# circuit1.net
KiCad netlist of a schematic drawn in EAGLE
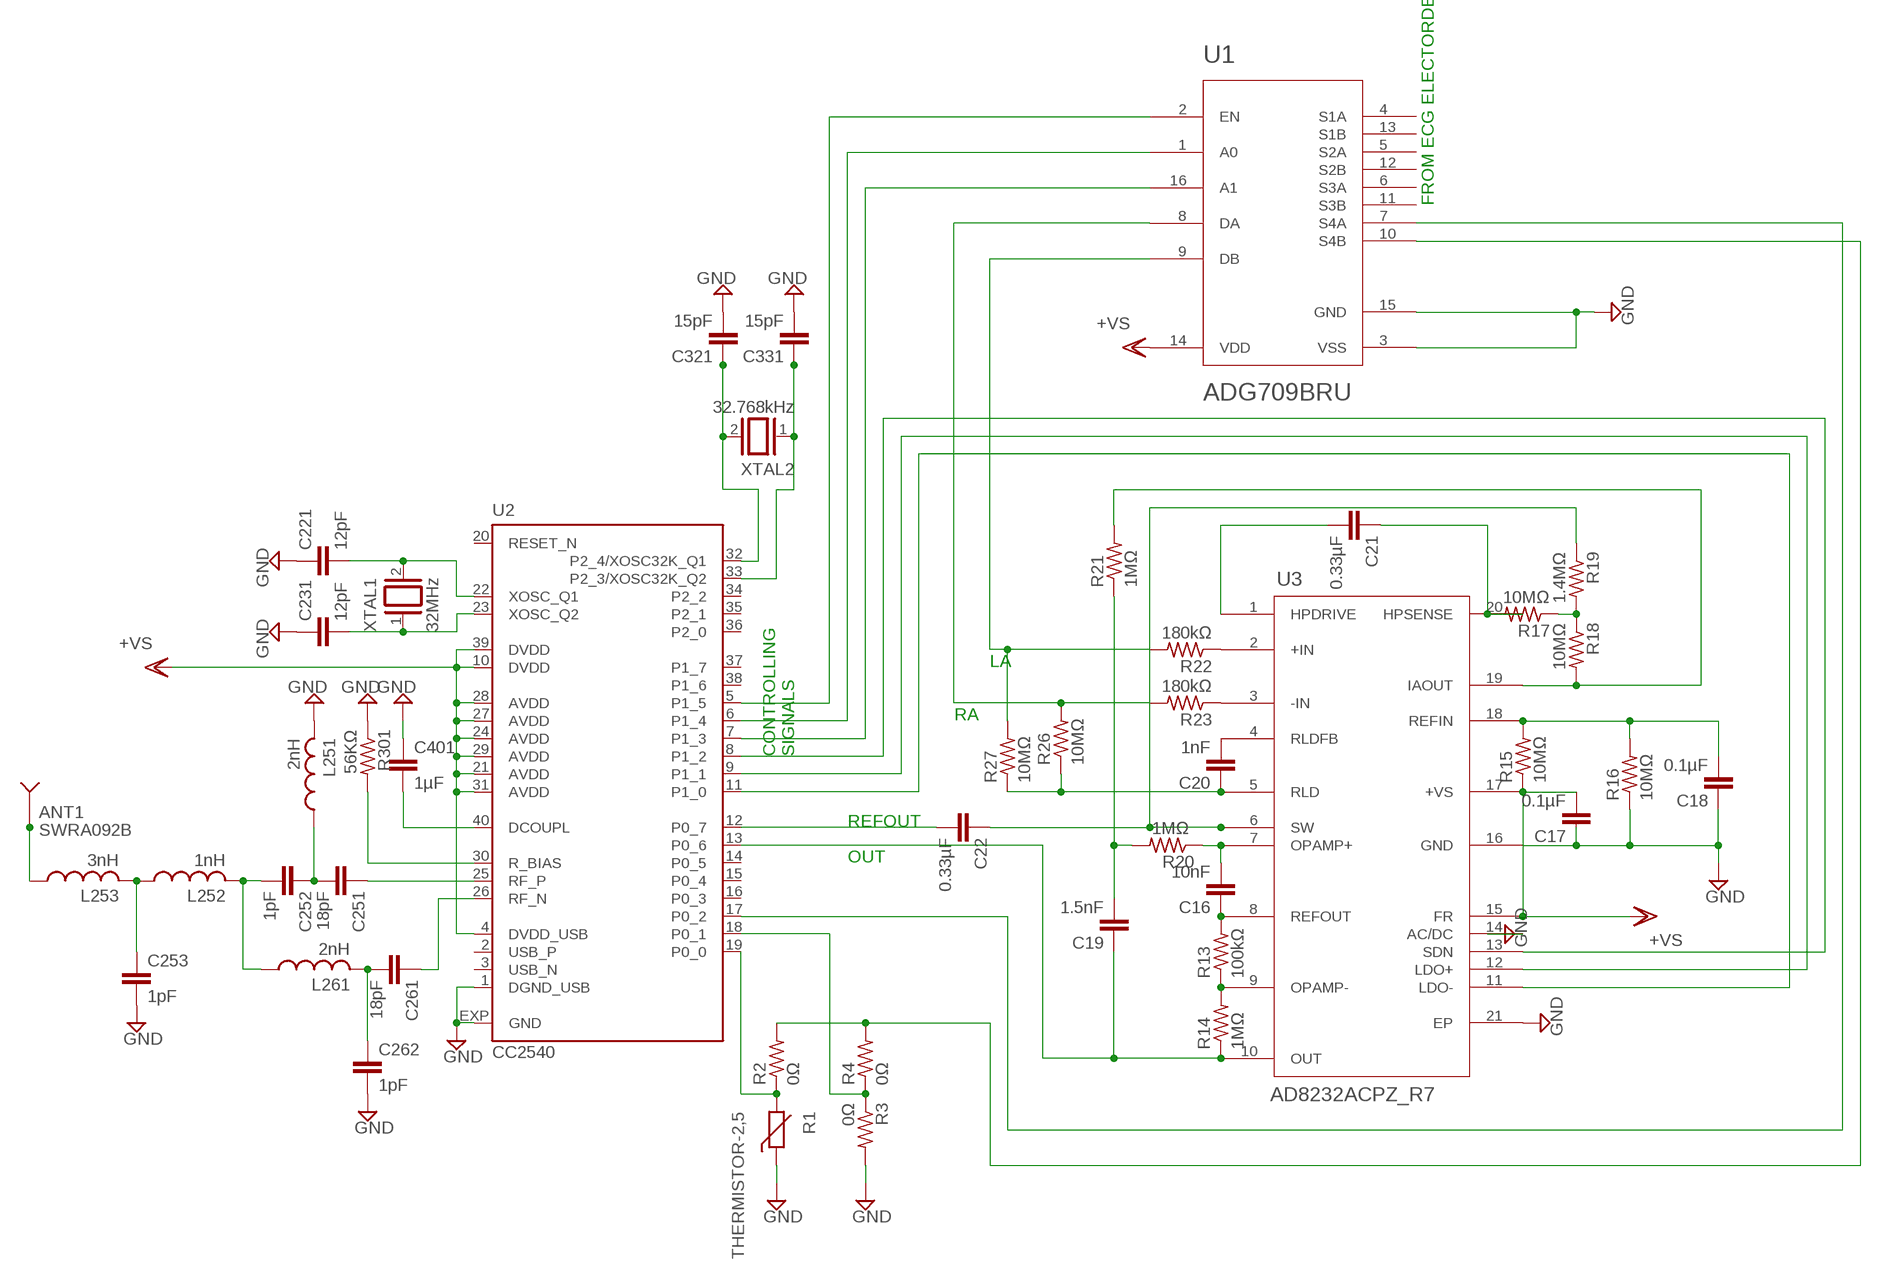
[diagram p0: schematic, sheet 1]

(export (version "E")
  (design (tool "Eeschema 10.0.6"))
  (components
    (comp (ref "ANT1")
      (value "SWRA092B")
      (footprint "eagle-import:SWRA092B")
      (libsource (lib "eagle-import") (part "SWRA092B"))
    )
    (comp (ref "C16")
      (value "10nF")
      (footprint "eagle-import:C0402")
      (libsource (lib "eagle-import") (part "C-EUC0402"))
    )
    (comp (ref "C17")
      (value "0.1µF")
      (footprint "eagle-import:C0402")
      (libsource (lib "eagle-import") (part "C-EUC0402"))
    )
    (comp (ref "C18")
      (value "0.1µF")
      (footprint "eagle-import:C0402")
      (libsource (lib "eagle-import") (part "C-EUC0402"))
    )
    (comp (ref "C19")
      (value "1.5nF")
      (footprint "eagle-import:C0402")
      (libsource (lib "eagle-import") (part "C-EUC0402"))
    )
    (comp (ref "C20")
      (value "1nF")
      (footprint "eagle-import:C0402")
      (libsource (lib "eagle-import") (part "C-EUC0402"))
    )
    (comp (ref "C21")
      (value "0.33µF")
      (footprint "eagle-import:C0402")
      (libsource (lib "eagle-import") (part "C-EUC0402"))
    )
    (comp (ref "C22")
      (value "0.33µF")
      (footprint "eagle-import:C0402")
      (libsource (lib "eagle-import") (part "C-EUC0402"))
    )
    (comp (ref "C221")
      (value "12pF")
      (footprint "eagle-import:C0402")
      (libsource (lib "eagle-import") (part "C-EUC0402"))
    )
    (comp (ref "C231")
      (value "12pF")
      (footprint "eagle-import:C0402")
      (libsource (lib "eagle-import") (part "C-EUC0402"))
    )
    (comp (ref "C251")
      (value "18pF")
      (footprint "eagle-import:C0402")
      (libsource (lib "eagle-import") (part "C-EUC0402"))
    )
    (comp (ref "C252")
      (value "1pF")
      (footprint "eagle-import:C0402")
      (libsource (lib "eagle-import") (part "C-EUC0402"))
    )
    (comp (ref "C253")
      (value "1pF")
      (footprint "eagle-import:C0402")
      (libsource (lib "eagle-import") (part "C-EUC0402"))
    )
    (comp (ref "C261")
      (value "18pF")
      (footprint "eagle-import:C0402")
      (libsource (lib "eagle-import") (part "C-EUC0402"))
    )
    (comp (ref "C262")
      (value "1pF")
      (footprint "eagle-import:C0402")
      (libsource (lib "eagle-import") (part "C-EUC0402"))
    )
    (comp (ref "C321")
      (value "15pF")
      (footprint "eagle-import:C0402")
      (libsource (lib "eagle-import") (part "C-EUC0402"))
    )
    (comp (ref "C331")
      (value "15pF")
      (footprint "eagle-import:C0402")
      (libsource (lib "eagle-import") (part "C-EUC0402"))
    )
    (comp (ref "C401")
      (value "1µF")
      (footprint "eagle-import:C0402")
      (libsource (lib "eagle-import") (part "C-EUC0402"))
    )
    (comp (ref "L251")
      (value "2nH")
      (footprint "eagle-import:0204_5")
      (libsource (lib "eagle-import") (part "L-US0204/5"))
    )
    (comp (ref "L252")
      (value "1nH")
      (footprint "eagle-import:0204_5")
      (libsource (lib "eagle-import") (part "L-US0204/5"))
    )
    (comp (ref "L253")
      (value "3nH")
      (footprint "eagle-import:0204_5")
      (libsource (lib "eagle-import") (part "L-US0204/5"))
    )
    (comp (ref "L261")
      (value "2nH")
      (footprint "eagle-import:0204_5")
      (libsource (lib "eagle-import") (part "L-US0204/5"))
    )
    (comp (ref "R1")
      (value "THERMISTOR-2,5")
      (footprint "eagle-import:RS-2,5")
      (libsource (lib "eagle-import") (part "THERMISTOR-2,5"))
    )
    (comp (ref "R2")
      (value "0Ω")
      (footprint "eagle-import:R0402")
      (libsource (lib "eagle-import") (part "R-US_R0402"))
    )
    (comp (ref "R3")
      (value "0Ω")
      (footprint "eagle-import:R0402")
      (libsource (lib "eagle-import") (part "R-US_R0402"))
    )
    (comp (ref "R4")
      (value "0Ω")
      (footprint "eagle-import:R0402")
      (libsource (lib "eagle-import") (part "R-US_R0402"))
    )
    (comp (ref "R13")
      (value "100kΩ")
      (footprint "eagle-import:R0402")
      (libsource (lib "eagle-import") (part "R-US_R0402"))
    )
    (comp (ref "R14")
      (value "1MΩ")
      (footprint "eagle-import:R0402")
      (libsource (lib "eagle-import") (part "R-US_R0402"))
    )
    (comp (ref "R15")
      (value "10MΩ")
      (footprint "eagle-import:R0402")
      (libsource (lib "eagle-import") (part "R-US_R0402"))
    )
    (comp (ref "R16")
      (value "10MΩ")
      (footprint "eagle-import:R0402")
      (libsource (lib "eagle-import") (part "R-US_R0402"))
    )
    (comp (ref "R17")
      (value "10MΩ")
      (footprint "eagle-import:R0402")
      (libsource (lib "eagle-import") (part "R-US_R0402"))
    )
    (comp (ref "R18")
      (value "10MΩ")
      (footprint "eagle-import:R0402")
      (libsource (lib "eagle-import") (part "R-US_R0402"))
    )
    (comp (ref "R19")
      (value "1.4MΩ")
      (footprint "eagle-import:R0402")
      (libsource (lib "eagle-import") (part "R-US_R0402"))
    )
    (comp (ref "R20")
      (value "1MΩ")
      (footprint "eagle-import:R0402")
      (libsource (lib "eagle-import") (part "R-US_R0402"))
    )
    (comp (ref "R21")
      (value "1MΩ")
      (footprint "eagle-import:R0402")
      (libsource (lib "eagle-import") (part "R-US_R0402"))
    )
    (comp (ref "R22")
      (value "180kΩ")
      (footprint "eagle-import:R0402")
      (libsource (lib "eagle-import") (part "R-US_R0402"))
    )
    (comp (ref "R23")
      (value "180kΩ")
      (footprint "eagle-import:R0402")
      (libsource (lib "eagle-import") (part "R-US_R0402"))
    )
    (comp (ref "R26")
      (value "10MΩ")
      (footprint "eagle-import:R0402")
      (libsource (lib "eagle-import") (part "R-US_R0402"))
    )
    (comp (ref "R27")
      (value "10MΩ")
      (footprint "eagle-import:R0402")
      (libsource (lib "eagle-import") (part "R-US_R0402"))
    )
    (comp (ref "R301")
      (value "56KΩ")
      (footprint "eagle-import:R0402")
      (libsource (lib "eagle-import") (part "R-US_R0402"))
    )
    (comp (ref "U1")
      (value "ADG709BRU")
      (footprint "eagle-import:RU_16")
      (libsource (lib "eagle-import") (part "ADG709BRU"))
    )
    (comp (ref "U2")
      (value "CC2540")
      (footprint "eagle-import:RHA_S-PVQFN-N40")
      (libsource (lib "eagle-import") (part "CC2540"))
    )
    (comp (ref "U3")
      (value "AD8232ACPZ_R7")
      (footprint "eagle-import:CP_20_10")
      (libsource (lib "eagle-import") (part "AD8232ACPZ_R7"))
    )
    (comp (ref "XTAL1")
      (value "32MHz")
      (footprint "eagle-import:Q")
      (libsource (lib "eagle-import") (part "XTAL"))
    )
    (comp (ref "XTAL2")
      (value "32.768kHz")
      (footprint "eagle-import:Q")
      (libsource (lib "eagle-import") (part "XTAL"))
    )
  )
  (nets
    (net (code "1") (name "+VS") (class "Default")
      (node (ref "C17") (pin "2") (pinfunction "2_2") (pintype "passive"))
      (node (ref "R15") (pin "1") (pinfunction "1_1") (pintype "passive"))
      (node (ref "U1") (pin "14") (pinfunction "VDD_14") (pintype "power_in"))
      (node (ref "U2") (pin "10") (pinfunction "DVDD_10") (pintype "power_in"))
      (node (ref "U2") (pin "21") (pinfunction "AVDD_21") (pintype "power_in"))
      (node (ref "U2") (pin "24") (pinfunction "AVDD_24") (pintype "power_in"))
      (node (ref "U2") (pin "27") (pinfunction "AVDD_27") (pintype "power_in"))
      (node (ref "U2") (pin "28") (pinfunction "AVDD_28") (pintype "power_in"))
      (node (ref "U2") (pin "29") (pinfunction "AVDD_29") (pintype "power_in"))
      (node (ref "U2") (pin "31") (pinfunction "AVDD_31") (pintype "power_in"))
      (node (ref "U2") (pin "39") (pinfunction "DVDD_39") (pintype "power_in"))
      (node (ref "U2") (pin "4") (pinfunction "DVDD_USB_4") (pintype "power_in"))
      (node (ref "U3") (pin "15") (pinfunction "FR_15") (pintype "passive"))
      (node (ref "U3") (pin "17") (pinfunction "+VS_17") (pintype "passive"))
    )
    (net (code "2") (name "GND") (class "Default")
      (node (ref "C17") (pin "1") (pinfunction "1_1") (pintype "passive"))
      (node (ref "C18") (pin "1") (pinfunction "1_1") (pintype "passive"))
      (node (ref "C221") (pin "1") (pinfunction "1_1") (pintype "passive"))
      (node (ref "C231") (pin "1") (pinfunction "1_1") (pintype "passive"))
      (node (ref "C253") (pin "2") (pinfunction "2_2") (pintype "passive"))
      (node (ref "C262") (pin "2") (pinfunction "2_2") (pintype "passive"))
      (node (ref "C321") (pin "2") (pinfunction "2_2") (pintype "passive"))
      (node (ref "C331") (pin "2") (pinfunction "2_2") (pintype "passive"))
      (node (ref "C401") (pin "1") (pinfunction "1_1") (pintype "passive"))
      (node (ref "L251") (pin "2") (pinfunction "2_2") (pintype "passive"))
      (node (ref "R1") (pin "1") (pinfunction "1_1") (pintype "passive"))
      (node (ref "R16") (pin "1") (pinfunction "1_1") (pintype "passive"))
      (node (ref "R3") (pin "2") (pinfunction "2_2") (pintype "passive"))
      (node (ref "R301") (pin "1") (pinfunction "1_1") (pintype "passive"))
      (node (ref "U1") (pin "15") (pinfunction "GND_15") (pintype "passive"))
      (node (ref "U1") (pin "3") (pinfunction "VSS_3") (pintype "power_in"))
      (node (ref "U2") (pin "1") (pinfunction "DGND_USB_1") (pintype "power_in"))
      (node (ref "U2") (pin "EXP") (pinfunction "GND_EXP") (pintype "passive"))
      (node (ref "U3") (pin "14") (pinfunction "AC/DC_14") (pintype "passive"))
      (node (ref "U3") (pin "16") (pinfunction "GND_16") (pintype "passive"))
      (node (ref "U3") (pin "21") (pinfunction "EP_21") (pintype "passive"))
    )
    (net (code "3") (name "Net-(ANT1-ANTENNA)") (class "Default")
      (node (ref "ANT1") (pin "1") (pinfunction "ANTENNA_1") (pintype "input"))
      (node (ref "L253") (pin "1") (pinfunction "1_1") (pintype "passive"))
    )
    (net (code "4") (name "Net-(C19-Pad2)") (class "Default")
      (node (ref "C19") (pin "2") (pinfunction "2_2") (pintype "passive"))
      (node (ref "R20") (pin "2") (pinfunction "2_2") (pintype "passive"))
      (node (ref "R21") (pin "1") (pinfunction "1_1") (pintype "passive"))
    )
    (net (code "5") (name "Net-(C251-Pad2)") (class "Default")
      (node (ref "C251") (pin "2") (pinfunction "2_2") (pintype "passive"))
      (node (ref "C252") (pin "1") (pinfunction "1_1") (pintype "passive"))
      (node (ref "L251") (pin "1") (pinfunction "1_1") (pintype "passive"))
    )
    (net (code "6") (name "Net-(C252-Pad2)") (class "Default")
      (node (ref "C252") (pin "2") (pinfunction "2_2") (pintype "passive"))
      (node (ref "L252") (pin "2") (pinfunction "2_2") (pintype "passive"))
      (node (ref "L261") (pin "1") (pinfunction "1_1") (pintype "passive"))
    )
    (net (code "7") (name "Net-(C253-Pad1)") (class "Default")
      (node (ref "C253") (pin "1") (pinfunction "1_1") (pintype "passive"))
      (node (ref "L252") (pin "1") (pinfunction "1_1") (pintype "passive"))
      (node (ref "L253") (pin "2") (pinfunction "2_2") (pintype "passive"))
    )
    (net (code "8") (name "Net-(C261-Pad2)") (class "Default")
      (node (ref "C261") (pin "2") (pinfunction "2_2") (pintype "passive"))
      (node (ref "C262") (pin "1") (pinfunction "1_1") (pintype "passive"))
      (node (ref "L261") (pin "2") (pinfunction "2_2") (pintype "passive"))
    )
    (net (code "9") (name "Net-(R17-Pad1)") (class "Default")
      (node (ref "R17") (pin "1") (pinfunction "1_1") (pintype "passive"))
      (node (ref "R18") (pin "1") (pinfunction "1_1") (pintype "passive"))
      (node (ref "R19") (pin "2") (pinfunction "2_2") (pintype "passive"))
    )
    (net (code "10") (name "Net-(U1-A0)") (class "Default")
      (node (ref "U1") (pin "1") (pinfunction "A0_1") (pintype "passive"))
      (node (ref "U2") (pin "6") (pinfunction "P1_4_6") (pintype "bidirectional"))
    )
    (net (code "11") (name "Net-(U1-A1)") (class "Default")
      (node (ref "U1") (pin "16") (pinfunction "A1_16") (pintype "passive"))
      (node (ref "U2") (pin "7") (pinfunction "P1_3_7") (pintype "bidirectional"))
    )
    (net (code "12") (name "Net-(U1-DA)") (class "Default")
      (node (ref "R23") (pin "2") (pinfunction "2_2") (pintype "passive"))
      (node (ref "R26") (pin "2") (pinfunction "2_2") (pintype "passive"))
      (node (ref "U1") (pin "8") (pinfunction "DA_8") (pintype "passive"))
    )
    (net (code "13") (name "Net-(U1-DB)") (class "Default")
      (node (ref "R22") (pin "2") (pinfunction "2_2") (pintype "passive"))
      (node (ref "R27") (pin "2") (pinfunction "2_2") (pintype "passive"))
      (node (ref "U1") (pin "9") (pinfunction "DB_9") (pintype "passive"))
    )
    (net (code "14") (name "Net-(U1-EN)") (class "Default")
      (node (ref "U1") (pin "2") (pinfunction "EN_2") (pintype "passive"))
      (node (ref "U2") (pin "5") (pinfunction "P1_5_5") (pintype "bidirectional"))
    )
    (net (code "15") (name "Net-(U1-S4A)") (class "Default")
      (node (ref "U1") (pin "7") (pinfunction "S4A_7") (pintype "passive"))
      (node (ref "U2") (pin "17") (pinfunction "P0_2_17") (pintype "bidirectional"))
    )
    (net (code "16") (name "Net-(U1-S4B)") (class "Default")
      (node (ref "R2") (pin "2") (pinfunction "2_2") (pintype "passive"))
      (node (ref "R4") (pin "2") (pinfunction "2_2") (pintype "passive"))
      (node (ref "U1") (pin "10") (pinfunction "S4B_10") (pintype "passive"))
    )
    (net (code "17") (name "Net-(U2-DCOUPL)") (class "Default")
      (node (ref "C401") (pin "2") (pinfunction "2_2") (pintype "passive"))
      (node (ref "U2") (pin "40") (pinfunction "DCOUPL_40") (pintype "power_in"))
    )
    (net (code "18") (name "Net-(U2-P0_0)") (class "Default")
      (node (ref "R1") (pin "2") (pinfunction "2_2") (pintype "passive"))
      (node (ref "R2") (pin "1") (pinfunction "1_1") (pintype "passive"))
      (node (ref "U2") (pin "19") (pinfunction "P0_0_19") (pintype "bidirectional"))
    )
    (net (code "19") (name "Net-(U2-P0_1)") (class "Default")
      (node (ref "R3") (pin "1") (pinfunction "1_1") (pintype "passive"))
      (node (ref "R4") (pin "1") (pinfunction "1_1") (pintype "passive"))
      (node (ref "U2") (pin "18") (pinfunction "P0_1_18") (pintype "bidirectional"))
    )
    (net (code "20") (name "Net-(U2-P0_6)") (class "Default")
      (node (ref "C19") (pin "1") (pinfunction "1_1") (pintype "passive"))
      (node (ref "R14") (pin "1") (pinfunction "1_1") (pintype "passive"))
      (node (ref "U2") (pin "13") (pinfunction "P0_6_13") (pintype "bidirectional"))
      (node (ref "U3") (pin "10") (pinfunction "OUT_10") (pintype "passive"))
    )
    (net (code "21") (name "Net-(U2-P0_7)") (class "Default")
      (node (ref "C22") (pin "2") (pinfunction "2_2") (pintype "passive"))
      (node (ref "U2") (pin "12") (pinfunction "P0_7_12") (pintype "bidirectional"))
    )
    (net (code "22") (name "Net-(U2-P1_0)") (class "Default")
      (node (ref "U2") (pin "11") (pinfunction "P1_0_11") (pintype "bidirectional"))
      (node (ref "U3") (pin "11") (pinfunction "LDO-_11") (pintype "passive"))
    )
    (net (code "23") (name "Net-(U2-P1_1)") (class "Default")
      (node (ref "U2") (pin "9") (pinfunction "P1_1_9") (pintype "bidirectional"))
      (node (ref "U3") (pin "12") (pinfunction "LDO+_12") (pintype "passive"))
    )
    (net (code "24") (name "Net-(U2-P1_2)") (class "Default")
      (node (ref "U2") (pin "8") (pinfunction "P1_2_8") (pintype "bidirectional"))
      (node (ref "U3") (pin "13") (pinfunction "SDN_13") (pintype "passive"))
    )
    (net (code "25") (name "Net-(U2-P2_3{slash}XOSC32K_Q2)") (class "Default")
      (node (ref "C331") (pin "1") (pinfunction "1_1") (pintype "passive"))
      (node (ref "U2") (pin "33") (pinfunction "P2_3/XOSC32K_Q2_33") (pintype "bidirectional"))
      (node (ref "XTAL2") (pin "1") (pinfunction "1_1") (pintype "passive"))
    )
    (net (code "26") (name "Net-(U2-P2_4{slash}XOSC32K_Q1)") (class "Default")
      (node (ref "C321") (pin "1") (pinfunction "1_1") (pintype "passive"))
      (node (ref "U2") (pin "32") (pinfunction "P2_4/XOSC32K_Q1_32") (pintype "bidirectional"))
      (node (ref "XTAL2") (pin "2") (pinfunction "2_2") (pintype "passive"))
    )
    (net (code "27") (name "Net-(U2-RF_N)") (class "Default")
      (node (ref "C261") (pin "1") (pinfunction "1_1") (pintype "passive"))
      (node (ref "U2") (pin "26") (pinfunction "RF_N_26") (pintype "bidirectional"))
    )
    (net (code "28") (name "Net-(U2-RF_P)") (class "Default")
      (node (ref "C251") (pin "1") (pinfunction "1_1") (pintype "passive"))
      (node (ref "U2") (pin "25") (pinfunction "RF_P_25") (pintype "bidirectional"))
    )
    (net (code "29") (name "Net-(U2-R_BIAS)") (class "Default")
      (node (ref "R301") (pin "2") (pinfunction "2_2") (pintype "passive"))
      (node (ref "U2") (pin "30") (pinfunction "R_BIAS_30") (pintype "bidirectional"))
    )
    (net (code "30") (name "Net-(U2-XOSC_Q1)") (class "Default")
      (node (ref "C221") (pin "2") (pinfunction "2_2") (pintype "passive"))
      (node (ref "U2") (pin "22") (pinfunction "XOSC_Q1_22") (pintype "bidirectional"))
      (node (ref "XTAL1") (pin "2") (pinfunction "2_2") (pintype "passive"))
    )
    (net (code "31") (name "Net-(U2-XOSC_Q2)") (class "Default")
      (node (ref "C231") (pin "2") (pinfunction "2_2") (pintype "passive"))
      (node (ref "U2") (pin "23") (pinfunction "XOSC_Q2_23") (pintype "bidirectional"))
      (node (ref "XTAL1") (pin "1") (pinfunction "1_1") (pintype "passive"))
    )
    (net (code "32") (name "Net-(U3-+IN)") (class "Default")
      (node (ref "R22") (pin "1") (pinfunction "1_1") (pintype "passive"))
      (node (ref "U3") (pin "2") (pinfunction "+IN_2") (pintype "passive"))
    )
    (net (code "33") (name "Net-(U3--IN)") (class "Default")
      (node (ref "R23") (pin "1") (pinfunction "1_1") (pintype "passive"))
      (node (ref "U3") (pin "3") (pinfunction "-IN_3") (pintype "passive"))
    )
    (net (code "34") (name "Net-(U3-HPDRIVE)") (class "Default")
      (node (ref "C21") (pin "2") (pinfunction "2_2") (pintype "passive"))
      (node (ref "U3") (pin "1") (pinfunction "HPDRIVE_1") (pintype "passive"))
    )
    (net (code "35") (name "Net-(U3-HPSENSE)") (class "Default")
      (node (ref "C21") (pin "1") (pinfunction "1_1") (pintype "passive"))
      (node (ref "R17") (pin "2") (pinfunction "2_2") (pintype "passive"))
      (node (ref "U3") (pin "20") (pinfunction "HPSENSE_20") (pintype "passive"))
    )
    (net (code "36") (name "Net-(U3-IAOUT)") (class "Default")
      (node (ref "R18") (pin "2") (pinfunction "2_2") (pintype "passive"))
      (node (ref "R21") (pin "2") (pinfunction "2_2") (pintype "passive"))
      (node (ref "U3") (pin "19") (pinfunction "IAOUT_19") (pintype "passive"))
    )
    (net (code "37") (name "Net-(U3-OPAMP+)") (class "Default")
      (node (ref "C16") (pin "2") (pinfunction "2_2") (pintype "passive"))
      (node (ref "R20") (pin "1") (pinfunction "1_1") (pintype "passive"))
      (node (ref "U3") (pin "7") (pinfunction "OPAMP+_7") (pintype "passive"))
    )
    (net (code "38") (name "Net-(U3-OPAMP-)") (class "Default")
      (node (ref "R13") (pin "1") (pinfunction "1_1") (pintype "passive"))
      (node (ref "R14") (pin "2") (pinfunction "2_2") (pintype "passive"))
      (node (ref "U3") (pin "9") (pinfunction "OPAMP-_9") (pintype "passive"))
    )
    (net (code "39") (name "Net-(U3-REFIN)") (class "Default")
      (node (ref "C18") (pin "2") (pinfunction "2_2") (pintype "passive"))
      (node (ref "R15") (pin "2") (pinfunction "2_2") (pintype "passive"))
      (node (ref "R16") (pin "2") (pinfunction "2_2") (pintype "passive"))
      (node (ref "U3") (pin "18") (pinfunction "REFIN_18") (pintype "passive"))
    )
    (net (code "40") (name "Net-(U3-REFOUT)") (class "Default")
      (node (ref "C16") (pin "1") (pinfunction "1_1") (pintype "passive"))
      (node (ref "R13") (pin "2") (pinfunction "2_2") (pintype "passive"))
      (node (ref "U3") (pin "8") (pinfunction "REFOUT_8") (pintype "passive"))
    )
    (net (code "41") (name "Net-(U3-RLD)") (class "Default")
      (node (ref "C20") (pin "1") (pinfunction "1_1") (pintype "passive"))
      (node (ref "R26") (pin "1") (pinfunction "1_1") (pintype "passive"))
      (node (ref "R27") (pin "1") (pinfunction "1_1") (pintype "passive"))
      (node (ref "U3") (pin "5") (pinfunction "RLD_5") (pintype "passive"))
    )
    (net (code "42") (name "Net-(U3-RLDFB)") (class "Default")
      (node (ref "C20") (pin "2") (pinfunction "2_2") (pintype "passive"))
      (node (ref "U3") (pin "4") (pinfunction "RLDFB_4") (pintype "passive"))
    )
    (net (code "43") (name "Net-(U3-SW)") (class "Default")
      (node (ref "C22") (pin "1") (pinfunction "1_1") (pintype "passive"))
      (node (ref "R19") (pin "1") (pinfunction "1_1") (pintype "passive"))
      (node (ref "U3") (pin "6") (pinfunction "SW_6") (pintype "passive"))
    )
    (net (code "44") (name "unconnected-(U1-S1A-Pad4)") (class "Default")
      (node (ref "U1") (pin "4") (pinfunction "S1A_4") (pintype "passive"))
    )
    (net (code "45") (name "unconnected-(U1-S1B-Pad13)") (class "Default")
      (node (ref "U1") (pin "13") (pinfunction "S1B_13") (pintype "passive"))
    )
    (net (code "46") (name "unconnected-(U1-S2A-Pad5)") (class "Default")
      (node (ref "U1") (pin "5") (pinfunction "S2A_5") (pintype "passive"))
    )
    (net (code "47") (name "unconnected-(U1-S2B-Pad12)") (class "Default")
      (node (ref "U1") (pin "12") (pinfunction "S2B_12") (pintype "passive"))
    )
    (net (code "48") (name "unconnected-(U1-S3A-Pad6)") (class "Default")
      (node (ref "U1") (pin "6") (pinfunction "S3A_6") (pintype "passive"))
    )
    (net (code "49") (name "unconnected-(U1-S3B-Pad11)") (class "Default")
      (node (ref "U1") (pin "11") (pinfunction "S3B_11") (pintype "passive"))
    )
    (net (code "50") (name "unconnected-(U2-P0_3-Pad16)") (class "Default")
      (node (ref "U2") (pin "16") (pinfunction "P0_3_16") (pintype "bidirectional"))
    )
    (net (code "51") (name "unconnected-(U2-P0_4-Pad15)") (class "Default")
      (node (ref "U2") (pin "15") (pinfunction "P0_4_15") (pintype "bidirectional"))
    )
    (net (code "52") (name "unconnected-(U2-P0_5-Pad14)") (class "Default")
      (node (ref "U2") (pin "14") (pinfunction "P0_5_14") (pintype "bidirectional"))
    )
    (net (code "53") (name "unconnected-(U2-P1_6-Pad38)") (class "Default")
      (node (ref "U2") (pin "38") (pinfunction "P1_6_38") (pintype "bidirectional"))
    )
    (net (code "54") (name "unconnected-(U2-P1_7-Pad37)") (class "Default")
      (node (ref "U2") (pin "37") (pinfunction "P1_7_37") (pintype "bidirectional"))
    )
    (net (code "55") (name "unconnected-(U2-P2_0-Pad36)") (class "Default")
      (node (ref "U2") (pin "36") (pinfunction "P2_0_36") (pintype "bidirectional"))
    )
    (net (code "56") (name "unconnected-(U2-P2_1-Pad35)") (class "Default")
      (node (ref "U2") (pin "35") (pinfunction "P2_1_35") (pintype "bidirectional"))
    )
    (net (code "57") (name "unconnected-(U2-P2_2-Pad34)") (class "Default")
      (node (ref "U2") (pin "34") (pinfunction "P2_2_34") (pintype "bidirectional"))
    )
    (net (code "58") (name "unconnected-(U2-RESET_N-Pad20)") (class "Default")
      (node (ref "U2") (pin "20") (pinfunction "RESET_N_20") (pintype "input"))
    )
    (net (code "59") (name "unconnected-(U2-USB_N-Pad3)") (class "Default")
      (node (ref "U2") (pin "3") (pinfunction "USB_N_3") (pintype "bidirectional"))
    )
    (net (code "60") (name "unconnected-(U2-USB_P-Pad2)") (class "Default")
      (node (ref "U2") (pin "2") (pinfunction "USB_P_2") (pintype "bidirectional"))
    )
  )
)
